# source_eagle.net
KiCad netlist of a schematic drawn in EAGLE
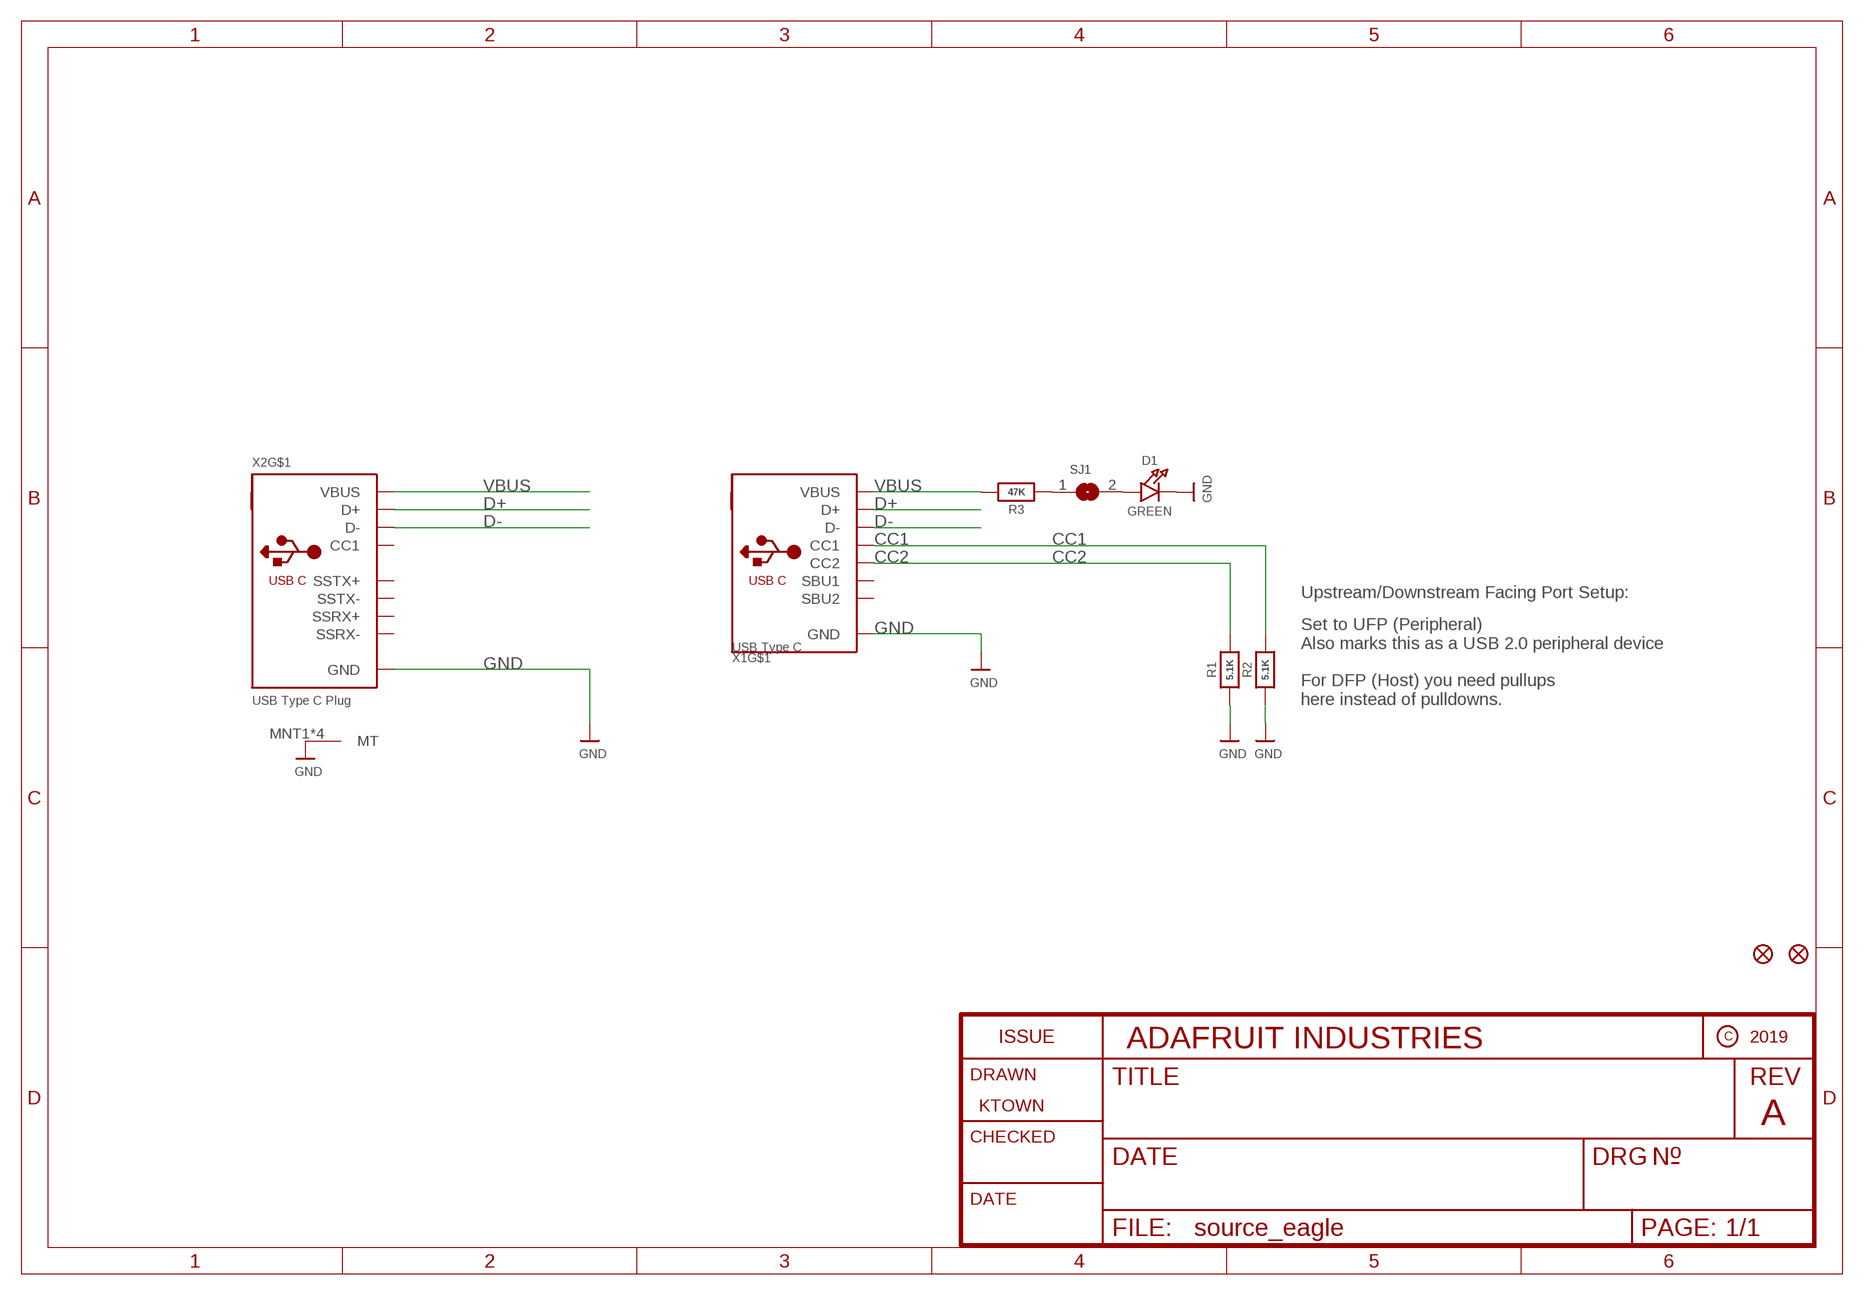
[diagram p0: schematic, sheet 1]

(export (version "E")
  (design (tool "Eeschema 10.0.6"))
  (components
    (comp (ref "D1")
      (value "GREEN")
      (footprint "eagle-import:CHIPLED_0603_NOOUTLINE")
      (libsource (lib "eagle-import") (part "LED0603_NOOUTLINE"))
    )
    (comp (ref "FID1")
      (value "FIDUCIAL_0.5MM")
      (footprint "eagle-import:FIDUCIAL_0.5MM")
      (libsource (lib "eagle-import") (part "FIDUCIAL_0.5MM"))
    )
    (comp (ref "FID2")
      (value "FIDUCIAL_0.5MM")
      (footprint "eagle-import:FIDUCIAL_0.5MM")
      (libsource (lib "eagle-import") (part "FIDUCIAL_0.5MM"))
    )
    (comp (ref "R1")
      (value "5.1K")
      (footprint "eagle-import:0603-NO")
      (libsource (lib "eagle-import") (part "RESISTOR_0603_NOOUT"))
    )
    (comp (ref "R2")
      (value "5.1K")
      (footprint "eagle-import:0603-NO")
      (libsource (lib "eagle-import") (part "RESISTOR_0603_NOOUT"))
    )
    (comp (ref "R3")
      (value "47K")
      (footprint "eagle-import:0603-NO")
      (libsource (lib "eagle-import") (part "RESISTOR_0603_NOOUT"))
    )
    (comp (ref "SJ1")
      (value "SOLDERJUMPERCLOSED")
      (footprint "eagle-import:SOLDERJUMPER_CLOSEDWIRE")
      (libsource (lib "eagle-import") (part "SOLDERJUMPERCLOSED"))
    )
    (comp (ref "X1")
      (value "USB Type C")
      (footprint "eagle-import:USB_C_SINK")
      (libsource (lib "eagle-import") (part "USB_C_SINK"))
    )
    (comp (ref "X2")
      (value "USB Type C Plug")
      (footprint "eagle-import:USB_TYPEC_PLUG_12P")
      (libsource (lib "eagle-import") (part "USB_C_PLUG_12P"))
    )
  )
  (nets
    (net (code "1") (name "/CC1") (class "Default")
      (node (ref "R2") (pin "2") (pinfunction "2_2") (pintype "passive"))
      (node (ref "X1") (pin "A5") (pinfunction "CC1_A5") (pintype "bidirectional"))
    )
    (net (code "2") (name "/CC2") (class "Default")
      (node (ref "R1") (pin "2") (pinfunction "2_2") (pintype "passive"))
      (node (ref "X1") (pin "B5") (pinfunction "CC2_B5") (pintype "bidirectional"))
    )
    (net (code "3") (name "/D+") (class "Default")
      (node (ref "X1") (pin "A6") (pinfunction "D+_A6") (pintype "bidirectional"))
      (node (ref "X1") (pin "B6") (pinfunction "D+_B6") (pintype "bidirectional"))
      (node (ref "X2") (pin "A6") (pinfunction "D+_A6") (pintype "bidirectional"))
    )
    (net (code "4") (name "/D-") (class "Default")
      (node (ref "X1") (pin "A7") (pinfunction "D-_A7") (pintype "bidirectional"))
      (node (ref "X1") (pin "B7") (pinfunction "D-_B7") (pintype "bidirectional"))
      (node (ref "X2") (pin "A7") (pinfunction "D-_A7") (pintype "bidirectional"))
    )
    (net (code "5") (name "/VBUS") (class "Default")
      (node (ref "R3") (pin "2") (pinfunction "2_2") (pintype "passive"))
      (node (ref "X1") (pin "A4B9") (pinfunction "VBUS_A4B9") (pintype "power_in"))
      (node (ref "X1") (pin "B4A9") (pinfunction "VBUS_B4A9") (pintype "power_in"))
      (node (ref "X2") (pin "A4") (pinfunction "VBUS_A4") (pintype "power_in"))
      (node (ref "X2") (pin "B9") (pinfunction "VBUS_B9") (pintype "power_in"))
    )
    (net (code "6") (name "GND") (class "Default")
      (node (ref "D1") (pin "C") (pinfunction "C_C") (pintype "passive"))
      (node (ref "R1") (pin "1") (pinfunction "1_1") (pintype "passive"))
      (node (ref "R2") (pin "1") (pinfunction "1_1") (pintype "passive"))
      (node (ref "X1") (pin "A1B12") (pinfunction "GND_A1B12") (pintype "power_in"))
      (node (ref "X1") (pin "B1A12") (pinfunction "GND_B1A12") (pintype "power_in"))
      (node (ref "X2") (pin "A1") (pinfunction "GND_A1") (pintype "power_in"))
      (node (ref "X2") (pin "A12") (pinfunction "GND_A12") (pintype "power_in"))
      (node (ref "X2") (pin "B12") (pinfunction "GND_B12") (pintype "power_in"))
      (node (ref "X2") (pin "MNT1") (pinfunction "MT_MNT1") (pintype "bidirectional"))
      (node (ref "X2") (pin "MNT2") (pinfunction "MT_MNT2") (pintype "bidirectional"))
      (node (ref "X2") (pin "P$1") (pinfunction "MT_P$1") (pintype "bidirectional"))
      (node (ref "X2") (pin "P$2") (pinfunction "MT_P$2") (pintype "bidirectional"))
    )
    (net (code "7") (name "Net-(D1-PadA)") (class "Default")
      (node (ref "D1") (pin "A") (pinfunction "A_A") (pintype "passive"))
      (node (ref "SJ1") (pin "2") (pinfunction "2_2") (pintype "passive"))
    )
    (net (code "8") (name "Net-(R3-Pad1)") (class "Default")
      (node (ref "R3") (pin "1") (pinfunction "1_1") (pintype "passive"))
      (node (ref "SJ1") (pin "1") (pinfunction "1_1") (pintype "passive"))
    )
    (net (code "9") (name "unconnected-(X1A-SBU1-PadA8)") (class "Default")
      (node (ref "X1") (pin "A8") (pinfunction "SBU1_A8") (pintype "bidirectional"))
    )
    (net (code "10") (name "unconnected-(X1A-SBU2-PadB8)") (class "Default")
      (node (ref "X1") (pin "B8") (pinfunction "SBU2_B8") (pintype "bidirectional"))
    )
    (net (code "11") (name "unconnected-(X2A-CC1-PadA5)") (class "Default")
      (node (ref "X2") (pin "A5") (pinfunction "CC1_A5") (pintype "bidirectional"))
    )
    (net (code "12") (name "unconnected-(X2A-SSRX+-PadB11)") (class "Default")
      (node (ref "X2") (pin "B11") (pinfunction "SSRX+_B11") (pintype "bidirectional"))
    )
    (net (code "13") (name "unconnected-(X2A-SSRX--PadB10)") (class "Default")
      (node (ref "X2") (pin "B10") (pinfunction "SSRX-_B10") (pintype "bidirectional"))
    )
    (net (code "14") (name "unconnected-(X2A-SSTX+-PadA2)") (class "Default")
      (node (ref "X2") (pin "A2") (pinfunction "SSTX+_A2") (pintype "bidirectional"))
    )
    (net (code "15") (name "unconnected-(X2A-SSTX--PadA3)") (class "Default")
      (node (ref "X2") (pin "A3") (pinfunction "SSTX-_A3") (pintype "bidirectional"))
    )
  )
)
